# door_sensor.net
KiCad netlist of a schematic drawn in EAGLE
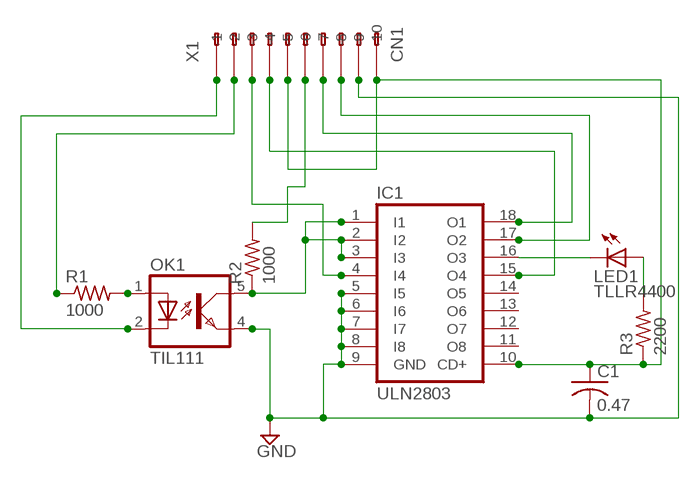
[diagram p0: schematic, sheet 1]

(export (version "E")
  (design (tool "Eeschema 10.0.6"))
  (components
    (comp (ref "C1")
      (value "0.47")
      (footprint "eagle-import:C025-024X044")
      (libsource (lib "eagle-import") (part "C-US025-024X044"))
    )
    (comp (ref "IC1")
      (value "ULN2803")
      (footprint "eagle-import:DIL18")
      (libsource (lib "eagle-import") (part "ULN2803A"))
    )
    (comp (ref "LED1")
      (value "TLLR4400")
      (footprint "eagle-import:LED3MM")
      (fields (field (name "MF") "VISHAY SEMICONDUCTOR"))
      (libsource (lib "eagle-import") (part "TLLR4400"))
    )
    (comp (ref "OK1")
      (value "TIL111")
      (footprint "eagle-import:DIL06")
      (fields (field (name "MF") "VISHAY/TELEFUNKEN") (field (name "MPN") "CNY17F-3"))
      (libsource (lib "eagle-import") (part "CNY17F"))
    )
    (comp (ref "R1")
      (value "1000")
      (footprint "eagle-import:0204V")
      (libsource (lib "eagle-import") (part "R-US_0204/2V"))
    )
    (comp (ref "R2")
      (value "1000")
      (footprint "eagle-import:0204V")
      (libsource (lib "eagle-import") (part "R-US_0204/2V"))
    )
    (comp (ref "R3")
      (value "2200")
      (footprint "eagle-import:0204V")
      (libsource (lib "eagle-import") (part "R-US_0204/2V"))
    )
    (comp (ref "X1")
      (value "CN1")
      (footprint "eagle-import:233-210")
      (fields (field (name "MPN") "233-210"))
      (libsource (lib "eagle-import") (part "233-210"))
    )
  )
  (nets
    (net (code "1") (name "GND") (class "Default")
      (node (ref "C1") (pin "2") (pinfunction "2_2") (pintype "passive"))
      (node (ref "IC1") (pin "5") (pinfunction "I5_5") (pintype "input"))
      (node (ref "IC1") (pin "6") (pinfunction "I6_6") (pintype "input"))
      (node (ref "IC1") (pin "7") (pinfunction "I7_7") (pintype "input"))
      (node (ref "IC1") (pin "8") (pinfunction "I8_8") (pintype "input"))
      (node (ref "IC1") (pin "9") (pinfunction "GND_9") (pintype "power_in"))
      (node (ref "OK1") (pin "4") (pinfunction "EMIT_4") (pintype "passive"))
      (node (ref "X1") (pin "A9") (pinfunction "-9_A9") (pintype "passive"))
    )
    (net (code "2") (name "Net-(IC1-CD+)") (class "Default")
      (node (ref "C1") (pin "1") (pinfunction "1_1") (pintype "passive"))
      (node (ref "IC1") (pin "10") (pinfunction "CD+_10") (pintype "passive"))
      (node (ref "R3") (pin "1") (pinfunction "1_1") (pintype "passive"))
      (node (ref "X1") (pin "A10") (pinfunction "-10_A10") (pintype "passive"))
      (node (ref "X1") (pin "A5") (pinfunction "-5_A5") (pintype "passive"))
    )
    (net (code "3") (name "Net-(IC1-I1)") (class "Default")
      (node (ref "IC1") (pin "1") (pinfunction "I1_1") (pintype "input"))
      (node (ref "IC1") (pin "2") (pinfunction "I2_2") (pintype "input"))
      (node (ref "IC1") (pin "3") (pinfunction "I3_3") (pintype "input"))
      (node (ref "OK1") (pin "5") (pinfunction "COL_5") (pintype "passive"))
      (node (ref "R2") (pin "1") (pinfunction "1_1") (pintype "passive"))
    )
    (net (code "4") (name "Net-(IC1-I4)") (class "Default")
      (node (ref "IC1") (pin "4") (pinfunction "I4_4") (pintype "input"))
      (node (ref "X1") (pin "A3") (pinfunction "-3_A3") (pintype "passive"))
    )
    (net (code "5") (name "Net-(IC1-O1)") (class "Default")
      (node (ref "IC1") (pin "18") (pinfunction "O1_18") (pintype "open_collector"))
      (node (ref "X1") (pin "A7") (pinfunction "-7_A7") (pintype "passive"))
    )
    (net (code "6") (name "Net-(IC1-O2)") (class "Default")
      (node (ref "IC1") (pin "17") (pinfunction "O2_17") (pintype "open_collector"))
      (node (ref "X1") (pin "A8") (pinfunction "-8_A8") (pintype "passive"))
    )
    (net (code "7") (name "Net-(IC1-O3)") (class "Default")
      (node (ref "IC1") (pin "16") (pinfunction "O3_16") (pintype "open_collector"))
      (node (ref "LED1") (pin "K") (pinfunction "C_K") (pintype "passive"))
    )
    (net (code "8") (name "Net-(IC1-O4)") (class "Default")
      (node (ref "IC1") (pin "15") (pinfunction "O4_15") (pintype "open_collector"))
      (node (ref "X1") (pin "A4") (pinfunction "-4_A4") (pintype "passive"))
    )
    (net (code "9") (name "Net-(LED1-PadA)") (class "Default")
      (node (ref "LED1") (pin "A") (pinfunction "A_A") (pintype "passive"))
      (node (ref "R3") (pin "2") (pinfunction "2_2") (pintype "passive"))
    )
    (net (code "10") (name "Net-(OK1-A)") (class "Default")
      (node (ref "OK1") (pin "1") (pinfunction "A_1") (pintype "passive"))
      (node (ref "R1") (pin "2") (pinfunction "2_2") (pintype "passive"))
    )
    (net (code "11") (name "Net-(OK1-C)") (class "Default")
      (node (ref "OK1") (pin "2") (pinfunction "C_2") (pintype "passive"))
      (node (ref "X1") (pin "A1") (pinfunction "-1_A1") (pintype "passive"))
    )
    (net (code "12") (name "Net-(X1--2)") (class "Default")
      (node (ref "R1") (pin "1") (pinfunction "1_1") (pintype "passive"))
      (node (ref "X1") (pin "A2") (pinfunction "-2_A2") (pintype "passive"))
    )
    (net (code "13") (name "Net-(X1--6)") (class "Default")
      (node (ref "R2") (pin "2") (pinfunction "2_2") (pintype "passive"))
      (node (ref "X1") (pin "A6") (pinfunction "-6_A6") (pintype "passive"))
    )
    (net (code "14") (name "unconnected-(IC1-O5-Pad14)") (class "Default")
      (node (ref "IC1") (pin "14") (pinfunction "O5_14") (pintype "open_collector"))
    )
    (net (code "15") (name "unconnected-(IC1-O6-Pad13)") (class "Default")
      (node (ref "IC1") (pin "13") (pinfunction "O6_13") (pintype "open_collector"))
    )
    (net (code "16") (name "unconnected-(IC1-O7-Pad12)") (class "Default")
      (node (ref "IC1") (pin "12") (pinfunction "O7_12") (pintype "open_collector"))
    )
    (net (code "17") (name "unconnected-(IC1-O8-Pad11)") (class "Default")
      (node (ref "IC1") (pin "11") (pinfunction "O8_11") (pintype "open_collector"))
    )
    (net (code "18") (name "unconnected-(X1-B-1-PadB1)") (class "Default")
      (node (ref "X1") (pin "B1") (pinfunction "B-1_B1") (pintype "passive"))
    )
    (net (code "19") (name "unconnected-(X1-B-2-PadB2)") (class "Default")
      (node (ref "X1") (pin "B2") (pinfunction "B-2_B2") (pintype "passive"))
    )
    (net (code "20") (name "unconnected-(X1-B-3-PadB3)") (class "Default")
      (node (ref "X1") (pin "B3") (pinfunction "B-3_B3") (pintype "passive"))
    )
    (net (code "21") (name "unconnected-(X1-B-4-PadB4)") (class "Default")
      (node (ref "X1") (pin "B4") (pinfunction "B-4_B4") (pintype "passive"))
    )
    (net (code "22") (name "unconnected-(X1-B-5-PadB5)") (class "Default")
      (node (ref "X1") (pin "B5") (pinfunction "B-5_B5") (pintype "passive"))
    )
    (net (code "23") (name "unconnected-(X1-B-6-PadB6)") (class "Default")
      (node (ref "X1") (pin "B6") (pinfunction "B-6_B6") (pintype "passive"))
    )
    (net (code "24") (name "unconnected-(X1-B-7-PadB7)") (class "Default")
      (node (ref "X1") (pin "B7") (pinfunction "B-7_B7") (pintype "passive"))
    )
    (net (code "25") (name "unconnected-(X1-B-8-PadB8)") (class "Default")
      (node (ref "X1") (pin "B8") (pinfunction "B-8_B8") (pintype "passive"))
    )
    (net (code "26") (name "unconnected-(X1-B-9-PadB9)") (class "Default")
      (node (ref "X1") (pin "B9") (pinfunction "B-9_B9") (pintype "passive"))
    )
    (net (code "27") (name "unconnected-(X1-B-10-PadB10)") (class "Default")
      (node (ref "X1") (pin "B10") (pinfunction "B-10_B10") (pintype "passive"))
    )
  )
)
